# H18R1_Backend.net
KiCad netlist of a schematic drawn in Altium Designer
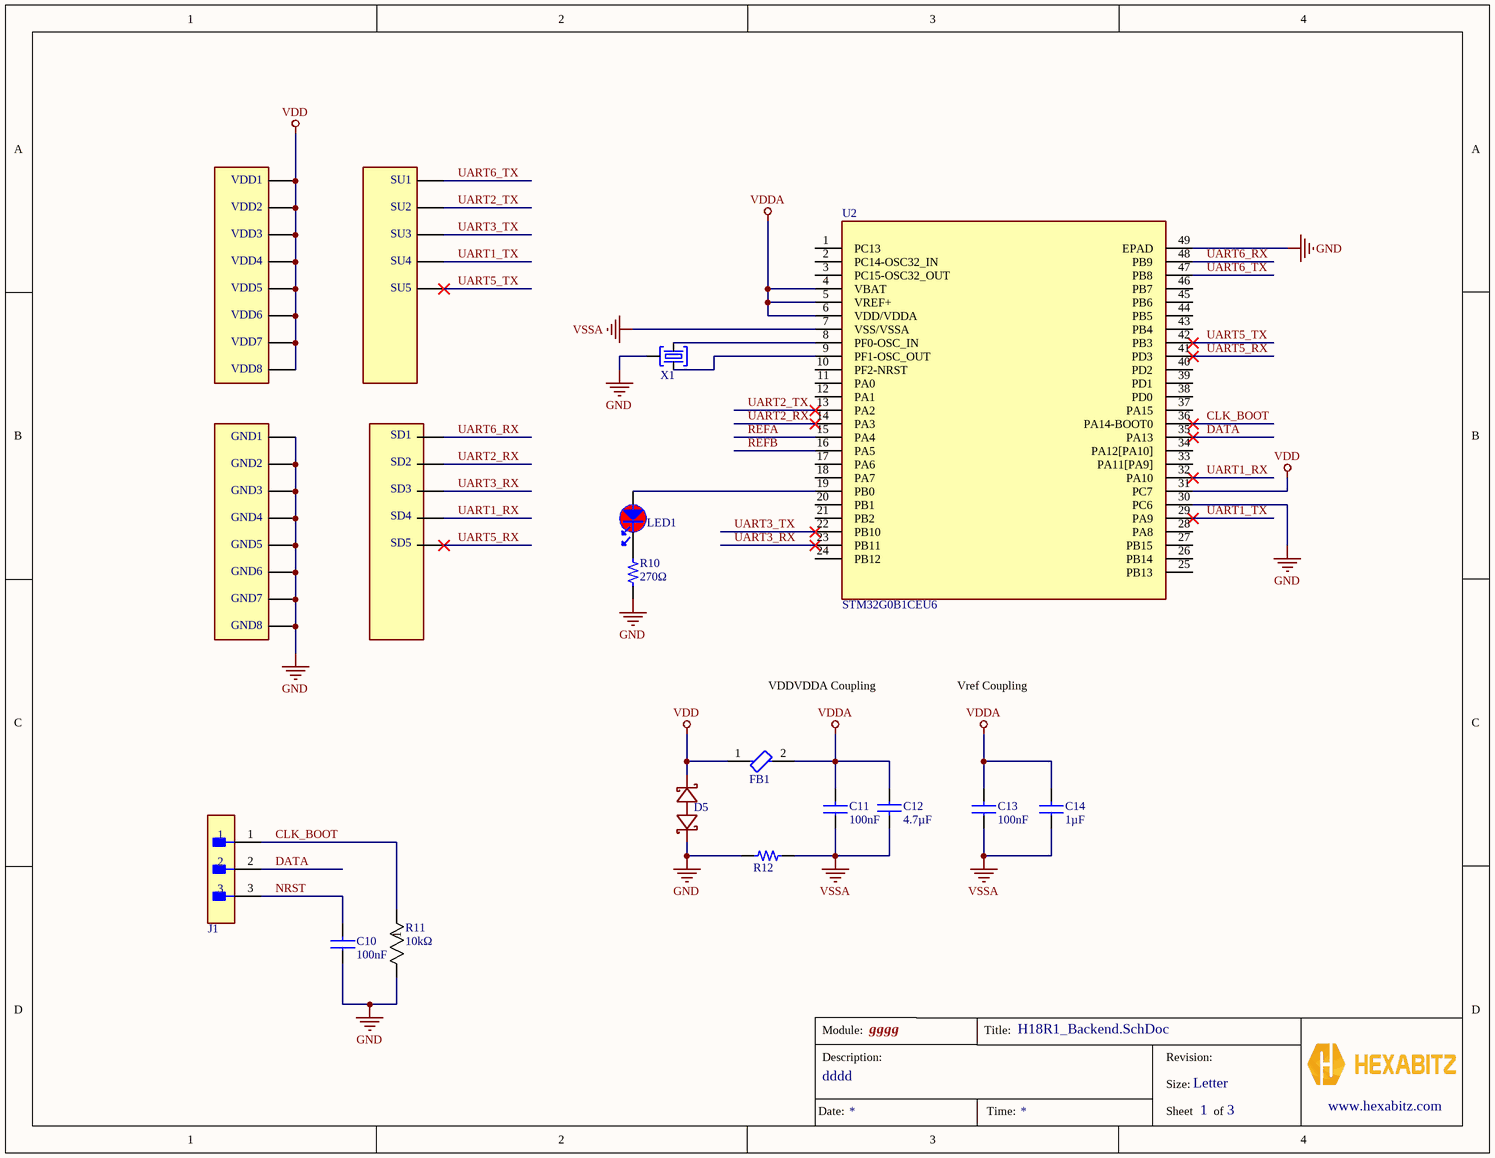
[diagram p0: H18R1_Backend.SchDoc]

(export (version "E")
  (design (tool "Eeschema 10.0.6"))
  (components
    (comp (ref "C10")
      (value "100nF")
      (footprint "C0603")
      (fields
        (field (name "MANUFACTURER") "Samsung Electro-Mechanics")
        (field (name "MANUFACTURER PART NUMBER") "CL10B104KA8NNNC")
        (field (name "TOLERANCE") "10%")
      )
      (libsource (lib "Hexabitz Altium Library") (part "generic Capacitor"))
    )
    (comp (ref "C11")
      (value "100nF")
      (footprint "C0603")
      (fields
        (field (name "MANUFACTURER") "Samsung Electro-Mechanics")
        (field (name "MANUFACTURER PART NUMBER") "CL10B104KA8NNNC")
        (field (name "TOLERANCE") "10%")
      )
      (libsource (lib "Hexabitz Altium Library") (part "generic Capacitor"))
    )
    (comp (ref "C12")
      (value "4.7µF")
      (footprint "C0805")
      (fields
        (field (name "MANUFACTURER") "Samsung Electro-Mechanics")
        (field (name "MANUFACTURER PART NUMBER") "CL21X475KAQNNNE")
        (field (name "TOLERANCE") "10%")
      )
      (libsource (lib "Hexabitz Altium Library") (part "generic Capacitor"))
    )
    (comp (ref "C13")
      (value "100nF")
      (footprint "C0603")
      (fields
        (field (name "MANUFACTURER") "Samsung Electro-Mechanics")
        (field (name "MANUFACTURER PART NUMBER") "CL10B104KA8NNNC")
        (field (name "TOLERANCE") "10%")
      )
      (libsource (lib "Hexabitz Altium Library") (part "generic Capacitor"))
    )
    (comp (ref "C14")
      (value "1µF")
      (footprint "C0805")
      (description "Ceramic Capacitor, Ceramic, 16V, 10% +Tol, 10% -Tol, X7R, 15% TC, 1uF, Surface Mount, 0805")
      (fields
        (field (name "MANUFACTURER") "Yageo Group")
        (field (name "MANUFACTURER PART NUMBER") "CC0805KKX7R7BB105")
      )
      (libsource (lib "Hexabitz Altium Library") (part "generic Capacitor"))
    )
    (comp (ref "D5")
      (value "CDSOD323-T03SC")
      (footprint "SOD2513X114N")
      (description "A 3V, 350W, bi-directional, standard capacitance, SOD323 pkg TVS Diode ¦ Bourns CDSOD323-T03SC")
      (fields (field (name "MANUFACTURER") "Bourns"))
      (libsource (lib "Hexabitz Altium Library") (part "CDSOD323-T03SC"))
    )
    (comp (ref "FB1")
      (value "MMZ1608Y300B")
      (footprint "FP-MMZ1608-0_8-MFG")
      (description "Ferrite Beads 0603 30ohms 1500mA Signal Line AEC-Q200")
      (fields
        (field (name "MANUFACTURER") "TDK")
        (field (name "MANUFACTURER PART NUMBER") "MMZ1608Y300BTD25")
      )
      (libsource (lib "Hexabitz Altium Library") (part "MMZ1608Y300B"))
    )
    (comp (ref "GND1")
      (value "HEXABIT_UART_PORT")
      (footprint "HEXABIT_POWER_PORT_D")
      (libsource (lib "hexabitz_connectors.Library") (part "HEXABIT_POWER_PORT_D_300R"))
    )
    (comp (ref "GND2")
      (value "HEXABIT_UART_PORT")
      (footprint "HEXABIT_POWER_PORT_D")
      (libsource (lib "hexabitz_connectors.Library") (part "HEXABIT_POWER_PORT_D"))
    )
    (comp (ref "GND3")
      (value "HEXABIT_UART_PORT")
      (footprint "HEXABIT_POWER_PORT_D")
      (libsource (lib "hexabitz_connectors.Library") (part "HEXABIT_POWER_PORT_D"))
    )
    (comp (ref "GND4")
      (value "HEXABIT_UART_PORT")
      (footprint "HEXABIT_POWER_PORT_D")
      (libsource (lib "hexabitz_connectors.Library") (part "HEXABIT_POWER_PORT_D"))
    )
    (comp (ref "GND5")
      (value "HEXABIT_UART_PORT")
      (footprint "HEXABIT_POWER_PORT_D")
      (libsource (lib "hexabitz_connectors.Library") (part "HEXABIT_POWER_PORT_D"))
    )
    (comp (ref "GND6")
      (value "HEXABIT_UART_PORT")
      (footprint "HEXABIT_POWER_PORT_D_300L")
      (libsource (lib "hexabitz_connectors.Library") (part "HEXABIT_POWER_PORT_D_300L"))
    )
    (comp (ref "GND7")
      (value "HEXABIT_UART_PORT")
      (footprint "HEXABIT_POWER_PORT_D")
      (libsource (lib "hexabitz_connectors.Library") (part "HEXABIT_POWER_PORT_D"))
    )
    (comp (ref "GND8")
      (value "HEXABIT_UART_PORT")
      (footprint "HEXABIT_POWER_PORT_D")
      (libsource (lib "hexabitz_connectors.Library") (part "HEXABIT_POWER_PORT_D"))
    )
    (comp (ref "J1")
      (value "TSW-103-14-G-S")
      (footprint "FP-TSW-103-14-G-S-MFG")
      (description "CONN HEADER VERT 3POS 2.54MM")
      (libsource (lib "Altium Content Vault") (part "cd3439d6ef35ae5d9b27ec4fdd3e828"))
    )
    (comp (ref "LED1")
      (value "VLMS1300-GS08")
      (footprint "FP-6_541-5092_01-4-MFG")
      (description "LED Uni-Color Super Red 639nm 2-Pin Chip 0603(1608Metric) T/R")
      (fields (field (name "MANUFACTURER") "Vishay Semiconductors"))
      (libsource (lib "Hexabitz Altium Library") (part "VLMS1300-GS08"))
    )
    (comp (ref "R10")
      (value "270Ω")
      (footprint "R0603")
      (description "Res Thick Film 0603 270 Ohm 5% 0.1W(1/10W) ±200ppm/C Pad SMD Automotive T/R")
      (fields
        (field (name "MANUFACTURER") "Panasonic")
        (field (name "MANUFACTURER PART NUMBER") "ERJ-3GEYJ271V")
      )
      (libsource (lib "") (part "generic Resistor_1"))
    )
    (comp (ref "R11")
      (value "10kΩ")
      (footprint "RC0603N_YAG")
      (description "RES SMD 10kO 1% 1/10W 0603")
      (fields
        (field (name "MANUFACTURER_PART_NUMBER") "RC0603FR-0710KL")
        (field (name "COPYRIGHT") "Copyright (C) 2025 Ultra Librarian. All rights reserved.")
      )
      (libsource (lib "H18R1") (part "RC0603FR-0710KL"))
    )
    (comp (ref "R12")
      (value "Manufacturer Part Number")
      (footprint "R0603")
      (libsource (lib "Hexabitz Altium Library") (part "generic Resistor"))
    )
    (comp (ref "SD1")
      (value "HEXABIT_UART_PORT")
      (footprint "HEXABIT_UART_PORT_D")
      (libsource (lib "hexabitz_connectors.Library") (part "HEXABIT_UART_PORT_D"))
    )
    (comp (ref "SD2")
      (value "HEXABIT_UART_PORT")
      (footprint "HEXABIT_UART_PORT_D")
      (libsource (lib "hexabitz_connectors.Library") (part "HEXABIT_UART_PORT_D"))
    )
    (comp (ref "SD3")
      (value "HEXABIT_UART_PORT")
      (footprint "HEXABIT_UART_PORT_D")
      (libsource (lib "hexabitz_connectors.Library") (part "HEXABIT_UART_PORT_D"))
    )
    (comp (ref "SD4")
      (value "HEXABIT_UART_PORT")
      (footprint "HEXABIT_UART_PORT_D")
      (libsource (lib "hexabitz_connectors.Library") (part "HEXABIT_UART_PORT_D"))
    )
    (comp (ref "SD5")
      (value "HEXABIT_UART_PORT")
      (footprint "HEXABIT_UART_PORT_D")
      (libsource (lib "hexabitz_connectors.Library") (part "HEXABIT_UART_PORT_D"))
    )
    (comp (ref "SU1")
      (value "HEXABIT_UART_PORT")
      (footprint "HEXABIT_UART_PORT_U")
      (libsource (lib "hexabitz_connectors.Library") (part "HEXABIT_UART_PORT_U"))
    )
    (comp (ref "SU2")
      (value "HEXABIT_UART_PORT")
      (footprint "HEXABIT_UART_PORT_U")
      (libsource (lib "hexabitz_connectors.Library") (part "HEXABIT_UART_PORT_U"))
    )
    (comp (ref "SU3")
      (value "HEXABIT_UART_PORT")
      (footprint "HEXABIT_UART_PORT_U")
      (libsource (lib "hexabitz_connectors.Library") (part "HEXABIT_UART_PORT_U"))
    )
    (comp (ref "SU4")
      (value "HEXABIT_UART_PORT")
      (footprint "HEXABIT_UART_PORT_U")
      (libsource (lib "hexabitz_connectors.Library") (part "HEXABIT_UART_PORT_U"))
    )
    (comp (ref "SU5")
      (value "HEXABIT_UART_PORT")
      (footprint "HEXABIT_UART_PORT_U")
      (libsource (lib "hexabitz_connectors.Library") (part "HEXABIT_UART_PORT_U"))
    )
    (comp (ref "U2")
      (value "STM32G0B1CEU6")
      (footprint "QFN50P700X700X65-49N-D")
      (description "MCU 32-bit ARM Cortex M0+ RISC 512KB Flash 1.8V/2.5V/3.3V 48-Pin UFQFPN EP Tray")
      (fields
        (field (name "MANUFACTURER") "STMicroelectronics")
        (field (name "MANUFACTURER PART NUMBER") "STM32G0B1CEU6")
      )
      (libsource (lib "Hexabitz Altium Library") (part "STM32G0B1CEU6"))
    )
    (comp (ref "VDD1")
      (value "HEXABIT_UART_PORT")
      (footprint "HEXABIT_POWER_PORT_U")
      (libsource (lib "hexabitz_connectors.Library") (part "HEXABIT_POWER_PORT_U"))
    )
    (comp (ref "VDD2")
      (value "HEXABIT_UART_PORT")
      (footprint "HEXABIT_POWER_PORT_U")
      (libsource (lib "hexabitz_connectors.Library") (part "HEXABIT_POWER_PORT_U"))
    )
    (comp (ref "VDD3")
      (value "HEXABIT_UART_PORT")
      (footprint "HEXABIT_POWER_PORT_U")
      (libsource (lib "hexabitz_connectors.Library") (part "HEXABIT_POWER_PORT_U_300R"))
    )
    (comp (ref "VDD4")
      (value "HEXABIT_UART_PORT")
      (footprint "HEXABIT_POWER_PORT_U")
      (libsource (lib "hexabitz_connectors.Library") (part "HEXABIT_POWER_PORT_U"))
    )
    (comp (ref "VDD5")
      (value "HEXABIT_UART_PORT")
      (footprint "HEXABIT_POWER_PORT_U")
      (libsource (lib "hexabitz_connectors.Library") (part "HEXABIT_POWER_PORT_U"))
    )
    (comp (ref "VDD6")
      (value "HEXABIT_UART_PORT")
      (footprint "HEXABIT_POWER_PORT_U")
      (libsource (lib "hexabitz_connectors.Library") (part "HEXABIT_POWER_PORT_U"))
    )
    (comp (ref "VDD7")
      (value "HEXABIT_UART_PORT")
      (footprint "HEXABIT_POWER_PORT_U")
      (libsource (lib "hexabitz_connectors.Library") (part "HEXABIT_POWER_PORT_U"))
    )
    (comp (ref "VDD8")
      (value "HEXABIT_UART_PORT")
      (footprint "HEXABIT_POWER_PORT_U_300L")
      (libsource (lib "hexabitz_connectors.Library") (part "HEXABIT_POWER_PORT_U_300L"))
    )
    (comp (ref "X1")
      (value "CSTCE8M00G52Z-R0")
      (footprint "XTALL_CSTCE8M00G52")
      (description "Ceramic Resonator 8MHz ±0.5% (Tol) ±0.2% (Stability) 10pF 40Ohm 3-Pin CSMD T/R")
      (fields (field (name "MANUFACTURER") "Murata") (field (name "TOLERANCE") "0.5%"))
      (libsource (lib "Hexabitz Altium Library") (part "CSTCE8M00G52Z-R0"))
    )
  )
  (nets
    (net (code "1") (name "/CLK_BOOT") (class "Default")
      (node (ref "J1") (pin "1") (pinfunction "1_1") (pintype "passive"))
      (node (ref "R11") (pin "1") (pinfunction "1_1") (pintype "passive"))
      (node (ref "U2") (pin "36") (pinfunction "PA14-BOOT0_36") (pintype "passive"))
    )
    (net (code "2") (name "/DATA") (class "Default")
      (node (ref "J1") (pin "2") (pinfunction "2_2") (pintype "passive"))
      (node (ref "U2") (pin "35") (pinfunction "PA13_35") (pintype "passive"))
    )
    (net (code "3") (name "/NRST") (class "Default")
      (node (ref "C10") (pin "2") (pinfunction "2_2") (pintype "passive"))
      (node (ref "J1") (pin "3") (pinfunction "3_3") (pintype "passive"))
    )
    (net (code "4") (name "/REFA") (class "Default")
      (node (ref "U2") (pin "15") (pinfunction "PA4_15") (pintype "passive"))
    )
    (net (code "5") (name "/REFB") (class "Default")
      (node (ref "U2") (pin "16") (pinfunction "PA5_16") (pintype "passive"))
    )
    (net (code "6") (name "/UART1_RX") (class "Default")
      (node (ref "SD4") (pin "UART_D") (pinfunction "UART_D_UART_D") (pintype "passive"))
      (node (ref "U2") (pin "32") (pinfunction "PA10_32") (pintype "passive"))
    )
    (net (code "7") (name "/UART1_TX") (class "Default")
      (node (ref "SU4") (pin "UART_U") (pinfunction "UART_U_UART_U") (pintype "passive"))
      (node (ref "U2") (pin "29") (pinfunction "PA9_29") (pintype "passive"))
    )
    (net (code "8") (name "/UART2_RX") (class "Default")
      (node (ref "SD2") (pin "UART_D") (pinfunction "UART_D_UART_D") (pintype "passive"))
      (node (ref "U2") (pin "14") (pinfunction "PA3_14") (pintype "passive"))
    )
    (net (code "9") (name "/UART2_TX") (class "Default")
      (node (ref "SU2") (pin "UART_U") (pinfunction "UART_U_UART_U") (pintype "passive"))
      (node (ref "U2") (pin "13") (pinfunction "PA2_13") (pintype "passive"))
    )
    (net (code "10") (name "/UART3_RX") (class "Default")
      (node (ref "SD3") (pin "UART_D") (pinfunction "UART_D_UART_D") (pintype "passive"))
      (node (ref "U2") (pin "23") (pinfunction "PB11_23") (pintype "passive"))
    )
    (net (code "11") (name "/UART3_TX") (class "Default")
      (node (ref "SU3") (pin "UART_U") (pinfunction "UART_U_UART_U") (pintype "passive"))
      (node (ref "U2") (pin "22") (pinfunction "PB10_22") (pintype "passive"))
    )
    (net (code "12") (name "/UART5_RX") (class "Default")
      (node (ref "SD5") (pin "UART_D") (pinfunction "UART_D_UART_D") (pintype "passive"))
      (node (ref "U2") (pin "41") (pinfunction "PD3_41") (pintype "passive"))
    )
    (net (code "13") (name "/UART5_TX") (class "Default")
      (node (ref "SU5") (pin "UART_U") (pinfunction "UART_U_UART_U") (pintype "passive"))
      (node (ref "U2") (pin "42") (pinfunction "PB3_42") (pintype "passive"))
    )
    (net (code "14") (name "/UART6_RX") (class "Default")
      (node (ref "SD1") (pin "UART_D") (pinfunction "UART_D_UART_D") (pintype "passive"))
      (node (ref "U2") (pin "48") (pinfunction "PB9_48") (pintype "passive"))
    )
    (net (code "15") (name "/UART6_TX") (class "Default")
      (node (ref "SU1") (pin "UART_U") (pinfunction "UART_U_UART_U") (pintype "passive"))
      (node (ref "U2") (pin "47") (pinfunction "PB8_47") (pintype "passive"))
    )
    (net (code "16") (name "GND") (class "Default")
      (node (ref "C10") (pin "1") (pinfunction "1_1") (pintype "passive"))
      (node (ref "D5") (pin "1") (pinfunction "A_1") (pintype "passive"))
      (node (ref "GND1") (pin "Pwr_D") (pinfunction "Pwr_D_Pwr_D") (pintype "passive"))
      (node (ref "GND2") (pin "Pwr_D") (pinfunction "Pwr_D_Pwr_D") (pintype "passive"))
      (node (ref "GND3") (pin "Pwr_D") (pinfunction "Pwr_D_Pwr_D") (pintype "passive"))
      (node (ref "GND4") (pin "Pwr_D") (pinfunction "Pwr_D_Pwr_D") (pintype "passive"))
      (node (ref "GND5") (pin "Pwr_D") (pinfunction "Pwr_D_Pwr_D") (pintype "passive"))
      (node (ref "GND6") (pin "Pwr_D") (pinfunction "Pwr_D_Pwr_D") (pintype "passive"))
      (node (ref "GND7") (pin "Pwr_D") (pinfunction "Pwr_D_Pwr_D") (pintype "passive"))
      (node (ref "GND8") (pin "Pwr_D") (pinfunction "Pwr_D_Pwr_D") (pintype "passive"))
      (node (ref "R10") (pin "1") (pinfunction "1_1") (pintype "passive"))
      (node (ref "R11") (pin "2") (pinfunction "2_2") (pintype "passive"))
      (node (ref "R12") (pin "1") (pinfunction "1_1") (pintype "passive"))
      (node (ref "U2") (pin "30") (pinfunction "PC6_30") (pintype "passive"))
      (node (ref "U2") (pin "49") (pinfunction "EPAD_49") (pintype "passive"))
      (node (ref "X1") (pin "P$2") (pinfunction "2_P$2") (pintype "passive"))
    )
    (net (code "17") (name "Net-(LED1-Pad1)") (class "Default")
      (node (ref "LED1") (pin "1") (pintype "passive"))
      (node (ref "R10") (pin "2") (pinfunction "2_2") (pintype "passive"))
    )
    (net (code "18") (name "Net-(U2-PB0)") (class "Default")
      (node (ref "LED1") (pin "2") (pintype "passive"))
      (node (ref "U2") (pin "19") (pinfunction "PB0_19") (pintype "passive"))
    )
    (net (code "19") (name "Net-(U2-PF0-OSC_IN)") (class "Default")
      (node (ref "U2") (pin "8") (pinfunction "PF0-OSC_IN_8") (pintype "passive"))
      (node (ref "X1") (pin "P$3") (pinfunction "3_P$3") (pintype "passive"))
    )
    (net (code "20") (name "Net-(U2-PF1-OSC_OUT)") (class "Default")
      (node (ref "U2") (pin "9") (pinfunction "PF1-OSC_OUT_9") (pintype "passive"))
      (node (ref "X1") (pin "P$1") (pinfunction "1_P$1") (pintype "passive"))
    )
    (net (code "21") (name "VDD") (class "Default")
      (node (ref "D5") (pin "2") (pinfunction "C_2") (pintype "passive"))
      (node (ref "FB1") (pin "1") (pinfunction "1_1") (pintype "passive"))
      (node (ref "U2") (pin "31") (pinfunction "PC7_31") (pintype "passive"))
      (node (ref "VDD1") (pin "Pwr_U") (pinfunction "Pwr_U_Pwr_U") (pintype "passive"))
      (node (ref "VDD2") (pin "Pwr_U") (pinfunction "Pwr_U_Pwr_U") (pintype "passive"))
      (node (ref "VDD3") (pin "Pwr_U") (pinfunction "Pwr_U_Pwr_U") (pintype "passive"))
      (node (ref "VDD4") (pin "Pwr_U") (pinfunction "Pwr_U_Pwr_U") (pintype "passive"))
      (node (ref "VDD5") (pin "Pwr_U") (pinfunction "Pwr_U_Pwr_U") (pintype "passive"))
      (node (ref "VDD6") (pin "Pwr_U") (pinfunction "Pwr_U_Pwr_U") (pintype "passive"))
      (node (ref "VDD7") (pin "Pwr_U") (pinfunction "Pwr_U_Pwr_U") (pintype "passive"))
      (node (ref "VDD8") (pin "Pwr_U") (pinfunction "Pwr_U_Pwr_U") (pintype "passive"))
    )
    (net (code "22") (name "VDDA") (class "Default")
      (node (ref "C11") (pin "2") (pinfunction "2_2") (pintype "passive"))
      (node (ref "C12") (pin "1") (pinfunction "1_1") (pintype "passive"))
      (node (ref "C13") (pin "2") (pinfunction "2_2") (pintype "passive"))
      (node (ref "C14") (pin "2") (pinfunction "2_2") (pintype "passive"))
      (node (ref "FB1") (pin "2") (pinfunction "2_2") (pintype "passive"))
      (node (ref "U2") (pin "4") (pinfunction "VBAT_4") (pintype "passive"))
      (node (ref "U2") (pin "5") (pinfunction "VREF+_5") (pintype "passive"))
      (node (ref "U2") (pin "6") (pinfunction "VDD/VDDA_6") (pintype "passive"))
    )
    (net (code "23") (name "VSSA") (class "Default")
      (node (ref "C11") (pin "1") (pinfunction "1_1") (pintype "passive"))
      (node (ref "C12") (pin "2") (pinfunction "2_2") (pintype "passive"))
      (node (ref "C13") (pin "1") (pinfunction "1_1") (pintype "passive"))
      (node (ref "C14") (pin "1") (pinfunction "1_1") (pintype "passive"))
      (node (ref "R12") (pin "2") (pinfunction "2_2") (pintype "passive"))
      (node (ref "U2") (pin "7") (pinfunction "VSS/VSSA_7") (pintype "passive"))
    )
    (net (code "24") (name "unconnected-(U2-PA0-Pad11)") (class "Default")
      (node (ref "U2") (pin "11") (pinfunction "PA0_11") (pintype "passive"))
    )
    (net (code "25") (name "unconnected-(U2-PA1-Pad12)") (class "Default")
      (node (ref "U2") (pin "12") (pinfunction "PA1_12") (pintype "passive"))
    )
    (net (code "26") (name "unconnected-(U2-PA6-Pad17)") (class "Default")
      (node (ref "U2") (pin "17") (pinfunction "PA6_17") (pintype "passive"))
    )
    (net (code "27") (name "unconnected-(U2-PA7-Pad18)") (class "Default")
      (node (ref "U2") (pin "18") (pinfunction "PA7_18") (pintype "passive"))
    )
    (net (code "28") (name "unconnected-(U2-PA8-Pad28)") (class "Default")
      (node (ref "U2") (pin "28") (pinfunction "PA8_28") (pintype "passive"))
    )
    (net (code "29") (name "unconnected-(U2-PA11[PA9]-Pad33)") (class "Default")
      (node (ref "U2") (pin "33") (pinfunction "PA11[PA9]_33") (pintype "passive"))
    )
    (net (code "30") (name "unconnected-(U2-PA12[PA10]-Pad34)") (class "Default")
      (node (ref "U2") (pin "34") (pinfunction "PA12[PA10]_34") (pintype "passive"))
    )
    (net (code "31") (name "unconnected-(U2-PA15-Pad37)") (class "Default")
      (node (ref "U2") (pin "37") (pinfunction "PA15_37") (pintype "passive"))
    )
    (net (code "32") (name "unconnected-(U2-PB1-Pad20)") (class "Default")
      (node (ref "U2") (pin "20") (pinfunction "PB1_20") (pintype "passive"))
    )
    (net (code "33") (name "unconnected-(U2-PB2-Pad21)") (class "Default")
      (node (ref "U2") (pin "21") (pinfunction "PB2_21") (pintype "passive"))
    )
    (net (code "34") (name "unconnected-(U2-PB4-Pad43)") (class "Default")
      (node (ref "U2") (pin "43") (pinfunction "PB4_43") (pintype "passive"))
    )
    (net (code "35") (name "unconnected-(U2-PB5-Pad44)") (class "Default")
      (node (ref "U2") (pin "44") (pinfunction "PB5_44") (pintype "passive"))
    )
    (net (code "36") (name "unconnected-(U2-PB6-Pad45)") (class "Default")
      (node (ref "U2") (pin "45") (pinfunction "PB6_45") (pintype "passive"))
    )
    (net (code "37") (name "unconnected-(U2-PB7-Pad46)") (class "Default")
      (node (ref "U2") (pin "46") (pinfunction "PB7_46") (pintype "passive"))
    )
    (net (code "38") (name "unconnected-(U2-PB12-Pad24)") (class "Default")
      (node (ref "U2") (pin "24") (pinfunction "PB12_24") (pintype "passive"))
    )
    (net (code "39") (name "unconnected-(U2-PB13-Pad25)") (class "Default")
      (node (ref "U2") (pin "25") (pinfunction "PB13_25") (pintype "passive"))
    )
    (net (code "40") (name "unconnected-(U2-PB14-Pad26)") (class "Default")
      (node (ref "U2") (pin "26") (pinfunction "PB14_26") (pintype "passive"))
    )
    (net (code "41") (name "unconnected-(U2-PB15-Pad27)") (class "Default")
      (node (ref "U2") (pin "27") (pinfunction "PB15_27") (pintype "passive"))
    )
    (net (code "42") (name "unconnected-(U2-PC13-Pad1)") (class "Default")
      (node (ref "U2") (pin "1") (pinfunction "PC13_1") (pintype "passive"))
    )
    (net (code "43") (name "unconnected-(U2-PC14-OSC32_IN-Pad2)") (class "Default")
      (node (ref "U2") (pin "2") (pinfunction "PC14-OSC32_IN_2") (pintype "passive"))
    )
    (net (code "44") (name "unconnected-(U2-PC15-OSC32_OUT-Pad3)") (class "Default")
      (node (ref "U2") (pin "3") (pinfunction "PC15-OSC32_OUT_3") (pintype "passive"))
    )
    (net (code "45") (name "unconnected-(U2-PD0-Pad38)") (class "Default")
      (node (ref "U2") (pin "38") (pinfunction "PD0_38") (pintype "passive"))
    )
    (net (code "46") (name "unconnected-(U2-PD1-Pad39)") (class "Default")
      (node (ref "U2") (pin "39") (pinfunction "PD1_39") (pintype "passive"))
    )
    (net (code "47") (name "unconnected-(U2-PD2-Pad40)") (class "Default")
      (node (ref "U2") (pin "40") (pinfunction "PD2_40") (pintype "passive"))
    )
    (net (code "48") (name "unconnected-(U2-PF2-NRST-Pad10)") (class "Default")
      (node (ref "U2") (pin "10") (pinfunction "PF2-NRST_10") (pintype "passive"))
    )
  )
)
